# micro.net
KiCad netlist of a schematic drawn in Altium Designer
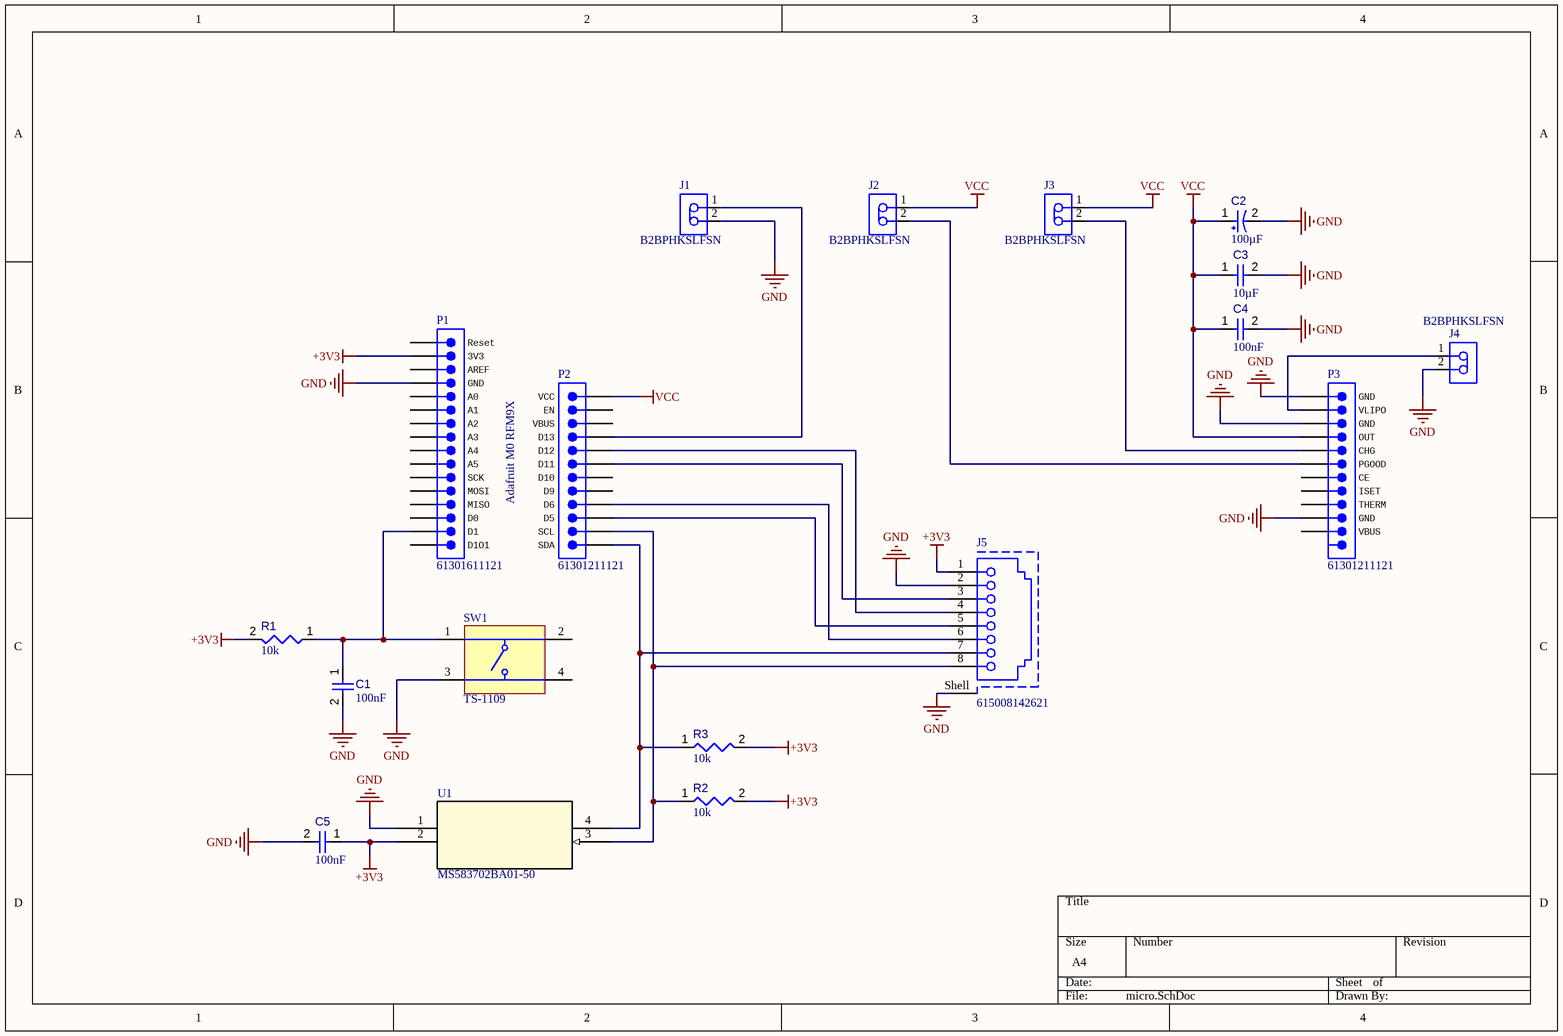
[diagram p0: micro.SchDoc]

(export (version "E")
  (design (tool "Eeschema 10.0.6"))
  (components
    (comp (ref "C1")
      (value "100nF")
      (footprint "CAPC2013X95X50LL10T25")
      (description "Chip Capacitor, 100 nF, +/- 10%, 50 V, 0805 (2012 Metric)")
      (fields (field (name "TOLERANCE") "10%") (field (name "Comment") "Capacitor 100 nF +/-10% 50 V 0805"))
      (libsource (lib "University of Auckland") (part "CAP-NP-2"))
    )
    (comp (ref "C2")
      (value "100µF")
      (footprint "CAPPR65-350-1150X800X1250")
      (description "Aluminum Electrolytic Capacitor, 100 uF, +/- 20%, 50 V, -40 to 85 degC, 2-Pin THD, RoHS, Bulk")
      (fields (field (name "MANUFACTURER") "Panasonic") (field (name "TOLERANCE") "20%"))
      (libsource (lib "University of Auckland") (part "CAP-P-2"))
    )
    (comp (ref "C3")
      (value "10µF")
      (footprint "CAPC0805(2012)145_L")
      (description "Chip Capacitor, 10µF +/-20%, 25V, 0805, Thickness 1.45 mm")
      (fields (field (name "TOLERANCE") "10%") (field (name "Comment") "Capacitor 10µF +/-20% 25V 0805"))
      (libsource (lib "University of Auckland") (part "CAP-NP-2"))
    )
    (comp (ref "C4")
      (value "100nF")
      (footprint "CAPC2013X95X50LL10T25")
      (description "Chip Capacitor, 100 nF, +/- 10%, 50 V, 0805 (2012 Metric)")
      (fields (field (name "TOLERANCE") "10%") (field (name "Comment") "Capacitor 100 nF +/-10% 50 V 0805"))
      (libsource (lib "University of Auckland") (part "CAP-NP-2"))
    )
    (comp (ref "C5")
      (value "100nF")
      (footprint "CAPC2013X95X50LL10T25")
      (description "Chip Capacitor, 100 nF, +/- 10%, 50 V, 0805 (2012 Metric)")
      (fields (field (name "TOLERANCE") "10%") (field (name "Comment") "Capacitor 100 nF +/-10% 50 V 0805"))
      (libsource (lib "University of Auckland") (part "CAP-NP-2"))
    )
    (comp (ref "J1")
      (value "B2BPHKSLFSN")
      (footprint "JST-B2B-PH-K-S_V")
      (description "Connector Header, PH Series, 2 Position, 2.00mm, Through Hole, Press-Fit, Solder, Natural")
      (libsource (lib "University of Auckland") (part "CN-2P-F-QF2"))
    )
    (comp (ref "J2")
      (value "B2BPHKSLFSN")
      (footprint "JST-B2B-PH-K-S_V")
      (description "Connector Header, PH Series, 2 Position, 2.00mm, Through Hole, Press-Fit, Solder, Natural")
      (libsource (lib "University of Auckland") (part "CN-2P-F-QF2"))
    )
    (comp (ref "J3")
      (value "B2BPHKSLFSN")
      (footprint "JST-B2B-PH-K-S_V")
      (description "Connector Header, PH Series, 2 Position, 2.00mm, Through Hole, Press-Fit, Solder, Natural")
      (libsource (lib "University of Auckland") (part "CN-2P-F-QF2"))
    )
    (comp (ref "J4")
      (value "B2BPHKSLFSN")
      (footprint "JST-B2B-PH-K-S_V")
      (description "Connector Header, PH Series, 2 Position, 2.00mm, Through Hole, Press-Fit, Solder, Natural")
      (libsource (lib "University of Auckland") (part "CN-2P-F-QF2"))
    )
    (comp (ref "J5")
      (value "615008142621")
      (footprint "615008142621")
      (description "Telecom and Datacom Connector, 8 Contact(s), Female, Right Angle, Solder Terminal, Locking, Jack")
      (libsource (lib "University of Auckland") (part "8P8C - 1 Port - Shielded"))
    )
    (comp (ref "P1")
      (value "61301611121")
      (footprint "61301611121")
      (libsource (lib "University of Auckland") (part "Header_Male_1R_16P"))
    )
    (comp (ref "P2")
      (value "61301211121")
      (footprint "61301211121")
      (libsource (lib "University of Auckland") (part "Header_Male_1R_12P"))
    )
    (comp (ref "P3")
      (value "61301211121")
      (footprint "61301211121")
      (libsource (lib "") (part "Header_Male_1R_12P_1"))
    )
    (comp (ref "R1")
      (value "10k")
      (footprint "RESC2013X50X35ML15T15")
      (description "Chip Resistor, 10 KOhm, +/- 1%, 125 mW, -55 to 155 degC, 0805 (2012 Metric)")
      (fields (field (name "TOLERANCE") "1%") (field (name "POWER") "125mW"))
      (libsource (lib "University of Auckland") (part "RES-2"))
    )
    (comp (ref "R2")
      (value "10k")
      (footprint "RESC2013X50X35ML15T15")
      (description "Chip Resistor, 10 KOhm, +/- 1%, 125 mW, -55 to 155 degC, 0805 (2012 Metric)")
      (fields (field (name "TOLERANCE") "1%") (field (name "POWER") "125mW"))
      (libsource (lib "University of Auckland") (part "RES-2"))
    )
    (comp (ref "R3")
      (value "10k")
      (footprint "RESC2013X50X35ML15T15")
      (description "Chip Resistor, 10 KOhm, +/- 1%, 125 mW, -55 to 155 degC, 0805 (2012 Metric)")
      (fields (field (name "TOLERANCE") "1%") (field (name "POWER") "125mW"))
      (libsource (lib "University of Auckland") (part "RES-2"))
    )
    (comp (ref "SW1")
      (value "TS-1109")
      (footprint "BEST-TS-1109_V")
      (description "Tactile Switch, SPST, 12 V, 50 mA, -20 to 80 degC, 4-Pin THD")
      (fields (field (name "MANUFACTURER") "Shenzhen Best"))
      (libsource (lib "University of Auckland") (part "SW-SPST-4_A"))
    )
    (comp (ref "U1")
      (value "MS583702BA01-50")
      (footprint "MS5837-02BA01_TEC")
      (description "No Description Available")
      (fields (field (name "COPYRIGHT") "Copyright (C) 2023 Ultra Librarian. All rights reserved."))
      (libsource (lib "University of Auckland") (part "MS583702BA01-50"))
    )
  )
  (nets
    (net (code "1") (name "+3V3") (class "Default")
      (node (ref "C5") (pin "1") (pinfunction "1_1") (pintype "passive"))
      (node (ref "J5") (pin "1") (pinfunction "1_1") (pintype "passive"))
      (node (ref "P1") (pin "2") (pinfunction "3V3_2") (pintype "passive"))
      (node (ref "R1") (pin "2") (pinfunction "2_2") (pintype "passive"))
      (node (ref "R2") (pin "2") (pinfunction "2_2") (pintype "passive"))
      (node (ref "R3") (pin "2") (pinfunction "2_2") (pintype "passive"))
      (node (ref "U1") (pin "2") (pinfunction "VDD_2") (pintype "power_in"))
    )
    (net (code "2") (name "GND") (class "Default")
      (node (ref "C1") (pin "2") (pinfunction "2_2") (pintype "passive"))
      (node (ref "C2") (pin "2") (pinfunction "2_2") (pintype "passive"))
      (node (ref "C3") (pin "2") (pinfunction "2_2") (pintype "passive"))
      (node (ref "C4") (pin "2") (pinfunction "2_2") (pintype "passive"))
      (node (ref "C5") (pin "2") (pinfunction "2_2") (pintype "passive"))
      (node (ref "J1") (pin "2") (pinfunction "2_2") (pintype "passive"))
      (node (ref "J4") (pin "2") (pinfunction "2_2") (pintype "passive"))
      (node (ref "J5") (pin "2") (pinfunction "2_2") (pintype "passive"))
      (node (ref "J5") (pin "Shell") (pinfunction "Shell_Shell") (pintype "passive"))
      (node (ref "P1") (pin "4") (pinfunction "GND_4") (pintype "passive"))
      (node (ref "P3") (pin "1") (pinfunction "GND_1") (pintype "passive"))
      (node (ref "P3") (pin "10") (pinfunction "GND_10") (pintype "passive"))
      (node (ref "P3") (pin "3") (pinfunction "GND_3") (pintype "passive"))
      (node (ref "SW1") (pin "3") (pinfunction "3_3") (pintype "passive"))
      (node (ref "U1") (pin "1") (pinfunction "GND_1") (pintype "power_in"))
    )
    (net (code "3") (name "Net-(P1-D1)") (class "Default")
      (node (ref "C1") (pin "1") (pinfunction "1_1") (pintype "passive"))
      (node (ref "P1") (pin "15") (pinfunction "D1_15") (pintype "passive"))
      (node (ref "R1") (pin "1") (pinfunction "1_1") (pintype "passive"))
      (node (ref "SW1") (pin "1") (pinfunction "1_1") (pintype "passive"))
    )
    (net (code "4") (name "Net-(P2-D5)") (class "Default")
      (node (ref "J5") (pin "5") (pinfunction "5_5") (pintype "passive"))
      (node (ref "P2") (pin "10") (pinfunction "D5_10") (pintype "passive"))
    )
    (net (code "5") (name "Net-(P2-D6)") (class "Default")
      (node (ref "J5") (pin "6") (pinfunction "6_6") (pintype "passive"))
      (node (ref "P2") (pin "9") (pinfunction "D6_9") (pintype "passive"))
    )
    (net (code "6") (name "Net-(P2-D11)") (class "Default")
      (node (ref "J5") (pin "3") (pinfunction "3_3") (pintype "passive"))
      (node (ref "P2") (pin "6") (pinfunction "D11_6") (pintype "passive"))
    )
    (net (code "7") (name "Net-(P2-D12)") (class "Default")
      (node (ref "J5") (pin "4") (pinfunction "4_4") (pintype "passive"))
      (node (ref "P2") (pin "5") (pinfunction "D12_5") (pintype "passive"))
    )
    (net (code "8") (name "Net-(P2-D13)") (class "Default")
      (node (ref "J1") (pin "1") (pinfunction "1_1") (pintype "passive"))
      (node (ref "P2") (pin "4") (pinfunction "D13_4") (pintype "passive"))
    )
    (net (code "9") (name "Net-(P2-SCL)") (class "Default")
      (node (ref "J5") (pin "8") (pinfunction "8_8") (pintype "passive"))
      (node (ref "P2") (pin "11") (pinfunction "SCL_11") (pintype "passive"))
      (node (ref "R2") (pin "1") (pinfunction "1_1") (pintype "passive"))
      (node (ref "U1") (pin "3") (pinfunction "SCL_3") (pintype "input"))
    )
    (net (code "10") (name "Net-(P2-SDA)") (class "Default")
      (node (ref "J5") (pin "7") (pinfunction "7_7") (pintype "passive"))
      (node (ref "P2") (pin "12") (pinfunction "SDA_12") (pintype "passive"))
      (node (ref "R3") (pin "1") (pinfunction "1_1") (pintype "passive"))
      (node (ref "U1") (pin "4") (pinfunction "SDA_4") (pintype "passive"))
    )
    (net (code "11") (name "Net-(P3-CHG)") (class "Default")
      (node (ref "J3") (pin "2") (pinfunction "2_2") (pintype "passive"))
      (node (ref "P3") (pin "5") (pinfunction "CHG_5") (pintype "passive"))
    )
    (net (code "12") (name "Net-(P3-PGOOD)") (class "Default")
      (node (ref "J2") (pin "2") (pinfunction "2_2") (pintype "passive"))
      (node (ref "P3") (pin "6") (pinfunction "PGOOD_6") (pintype "passive"))
    )
    (net (code "13") (name "Net-(P3-VLIPO)") (class "Default")
      (node (ref "J4") (pin "1") (pinfunction "1_1") (pintype "passive"))
      (node (ref "P3") (pin "2") (pinfunction "VLIPO_2") (pintype "passive"))
    )
    (net (code "14") (name "VCC") (class "Default")
      (node (ref "C2") (pin "1") (pinfunction "1_1") (pintype "passive"))
      (node (ref "C3") (pin "1") (pinfunction "1_1") (pintype "passive"))
      (node (ref "C4") (pin "1") (pinfunction "1_1") (pintype "passive"))
      (node (ref "J2") (pin "1") (pinfunction "1_1") (pintype "passive"))
      (node (ref "J3") (pin "1") (pinfunction "1_1") (pintype "passive"))
      (node (ref "P2") (pin "1") (pinfunction "VCC_1") (pintype "passive"))
      (node (ref "P3") (pin "4") (pinfunction "OUT_4") (pintype "passive"))
    )
    (net (code "15") (name "unconnected-(P1-A0-Pad5)") (class "Default")
      (node (ref "P1") (pin "5") (pinfunction "A0_5") (pintype "passive"))
    )
    (net (code "16") (name "unconnected-(P1-A1-Pad6)") (class "Default")
      (node (ref "P1") (pin "6") (pinfunction "A1_6") (pintype "passive"))
    )
    (net (code "17") (name "unconnected-(P1-A2-Pad7)") (class "Default")
      (node (ref "P1") (pin "7") (pinfunction "A2_7") (pintype "passive"))
    )
    (net (code "18") (name "unconnected-(P1-A3-Pad8)") (class "Default")
      (node (ref "P1") (pin "8") (pinfunction "A3_8") (pintype "passive"))
    )
    (net (code "19") (name "unconnected-(P1-A4-Pad9)") (class "Default")
      (node (ref "P1") (pin "9") (pinfunction "A4_9") (pintype "passive"))
    )
    (net (code "20") (name "unconnected-(P1-A5-Pad10)") (class "Default")
      (node (ref "P1") (pin "10") (pinfunction "A5_10") (pintype "passive"))
    )
    (net (code "21") (name "unconnected-(P1-AREF-Pad3)") (class "Default")
      (node (ref "P1") (pin "3") (pinfunction "AREF_3") (pintype "passive"))
    )
    (net (code "22") (name "unconnected-(P1-D0-Pad14)") (class "Default")
      (node (ref "P1") (pin "14") (pinfunction "D0_14") (pintype "passive"))
    )
    (net (code "23") (name "unconnected-(P1-D1O1-Pad16)") (class "Default")
      (node (ref "P1") (pin "16") (pinfunction "D1O1_16") (pintype "passive"))
    )
    (net (code "24") (name "unconnected-(P1-MISO-Pad13)") (class "Default")
      (node (ref "P1") (pin "13") (pinfunction "MISO_13") (pintype "passive"))
    )
    (net (code "25") (name "unconnected-(P1-MOSI-Pad12)") (class "Default")
      (node (ref "P1") (pin "12") (pinfunction "MOSI_12") (pintype "passive"))
    )
    (net (code "26") (name "unconnected-(P1-Reset-Pad1)") (class "Default")
      (node (ref "P1") (pin "1") (pinfunction "Reset_1") (pintype "passive"))
    )
    (net (code "27") (name "unconnected-(P1-SCK-Pad11)") (class "Default")
      (node (ref "P1") (pin "11") (pinfunction "SCK_11") (pintype "passive"))
    )
    (net (code "28") (name "unconnected-(P2-D9-Pad8)") (class "Default")
      (node (ref "P2") (pin "8") (pinfunction "D9_8") (pintype "passive"))
    )
    (net (code "29") (name "unconnected-(P2-D10-Pad7)") (class "Default")
      (node (ref "P2") (pin "7") (pinfunction "D10_7") (pintype "passive"))
    )
    (net (code "30") (name "unconnected-(P2-EN-Pad2)") (class "Default")
      (node (ref "P2") (pin "2") (pinfunction "EN_2") (pintype "passive"))
    )
    (net (code "31") (name "unconnected-(P2-VBUS-Pad3)") (class "Default")
      (node (ref "P2") (pin "3") (pinfunction "VBUS_3") (pintype "passive"))
    )
    (net (code "32") (name "unconnected-(P3-CE-Pad7)") (class "Default")
      (node (ref "P3") (pin "7") (pinfunction "CE_7") (pintype "passive"))
    )
    (net (code "33") (name "unconnected-(P3-ISET-Pad8)") (class "Default")
      (node (ref "P3") (pin "8") (pinfunction "ISET_8") (pintype "passive"))
    )
    (net (code "34") (name "unconnected-(P3-THERM-Pad9)") (class "Default")
      (node (ref "P3") (pin "9") (pinfunction "THERM_9") (pintype "passive"))
    )
    (net (code "35") (name "unconnected-(P3-VBUS-Pad11)") (class "Default")
      (node (ref "P3") (pin "11") (pinfunction "VBUS_11") (pintype "passive"))
    )
    (net (code "36") (name "unconnected-(SW1-Pad2)") (class "Default")
      (node (ref "SW1") (pin "2") (pinfunction "2_2") (pintype "passive"))
    )
    (net (code "37") (name "unconnected-(SW1-Pad4)") (class "Default")
      (node (ref "SW1") (pin "4") (pinfunction "4_4") (pintype "passive"))
    )
  )
)
